# FPGA_7A35T.net
KiCad netlist of a schematic drawn in Altium Designer
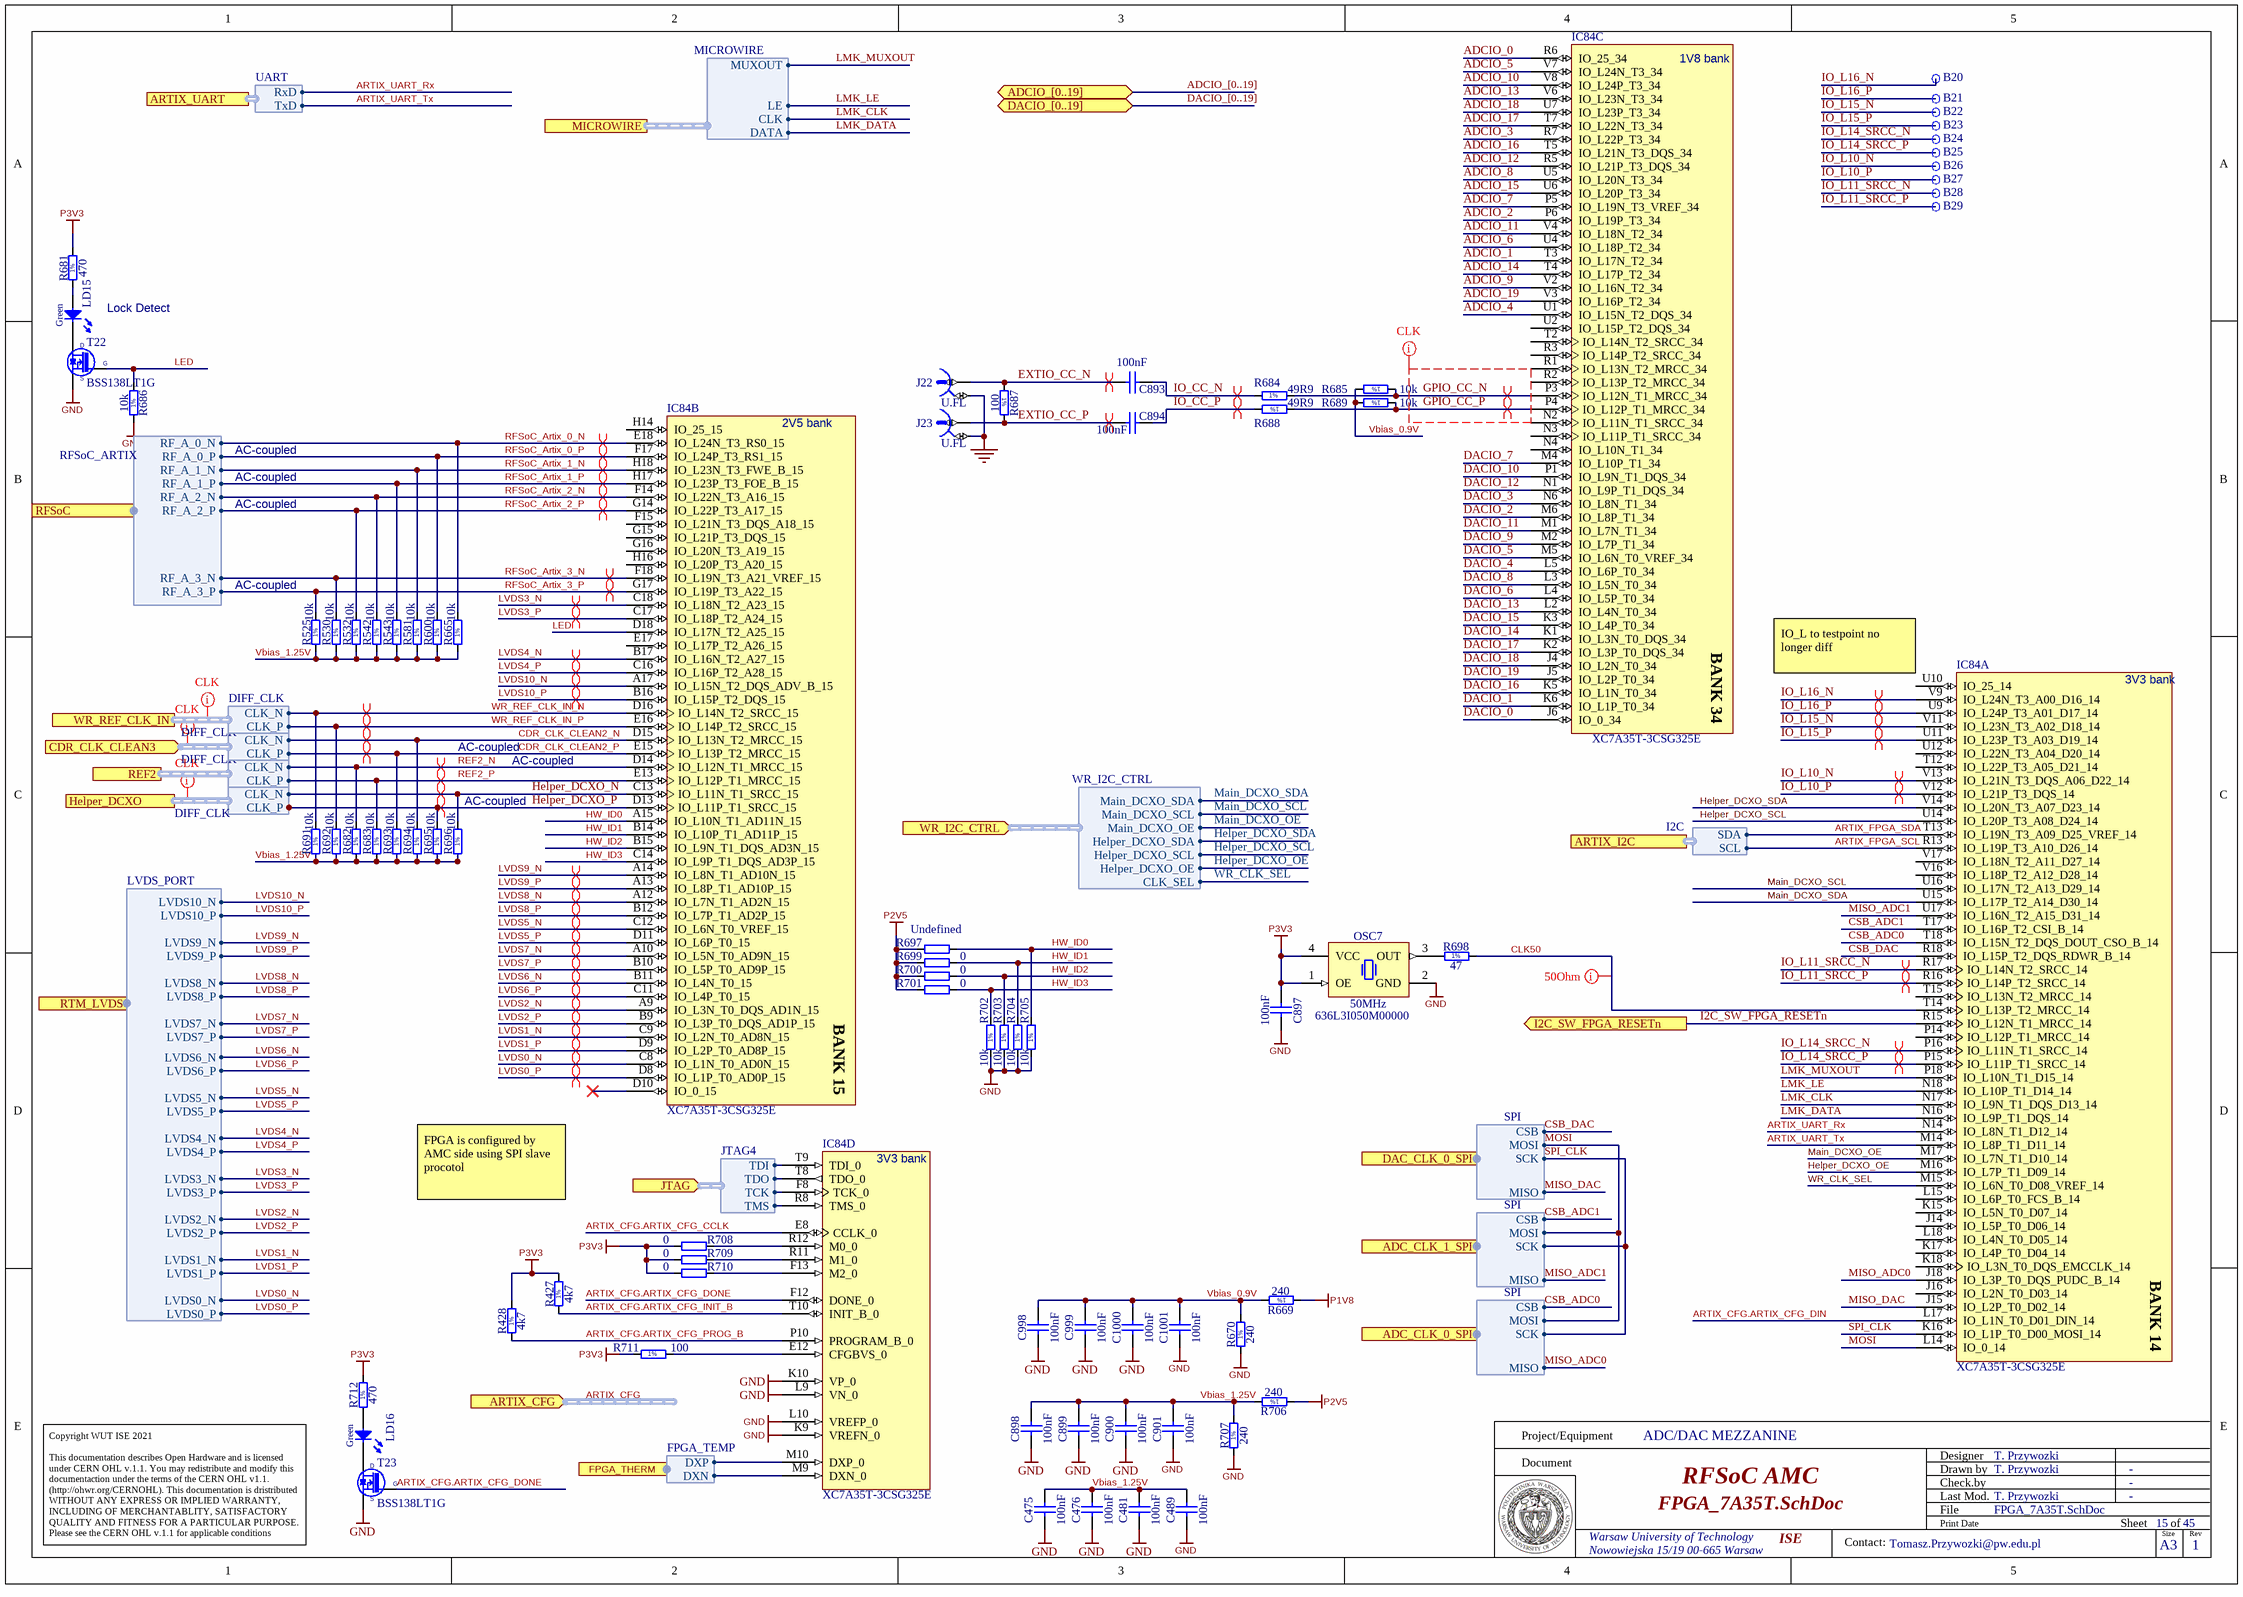
[diagram p0: FPGA_7A35T.SchDoc]

(export (version "E")
  (design (tool "Eeschema 10.0.6"))
  (components
    (comp (ref "B20")
      (value "SMD_PAD_D1MM")
      (footprint "C100")
      (libsource (lib "altium-import") (part "root_0__*"))
    )
    (comp (ref "B21")
      (value "SMD_PAD_D1MM")
      (footprint "C100")
      (libsource (lib "altium-import") (part "root_0__*"))
    )
    (comp (ref "B22")
      (value "SMD_PAD_D1MM")
      (footprint "C100")
      (libsource (lib "altium-import") (part "root_0__*"))
    )
    (comp (ref "B23")
      (value "SMD_PAD_D1MM")
      (footprint "C100")
      (libsource (lib "altium-import") (part "root_0__*"))
    )
    (comp (ref "B24")
      (value "SMD_PAD_D1MM")
      (footprint "C100")
      (libsource (lib "altium-import") (part "root_0__*"))
    )
    (comp (ref "B25")
      (value "SMD_PAD_D1MM")
      (footprint "C100")
      (libsource (lib "altium-import") (part "root_0__*"))
    )
    (comp (ref "B26")
      (value "SMD_PAD_D1MM")
      (footprint "C100")
      (libsource (lib "altium-import") (part "root_0__*"))
    )
    (comp (ref "B27")
      (value "SMD_PAD_D1MM")
      (footprint "C100")
      (libsource (lib "altium-import") (part "root_0__*"))
    )
    (comp (ref "B28")
      (value "SMD_PAD_D1MM")
      (footprint "C100")
      (libsource (lib "altium-import") (part "root_0__*"))
    )
    (comp (ref "B29")
      (value "SMD_PAD_D1MM")
      (footprint "C100")
      (libsource (lib "altium-import") (part "root_0__*"))
    )
    (comp (ref "C475")
      (value "100nF")
      (footprint "CAPC0603X33N")
      (description "Non-polarised capacitor")
      (fields
        (field (name "MANUFACTURER PART NUMBER") "CC0201_100NF_6.3V_10%_X5R")
        (field (name "MANUFACTURER") "GENERIC")
        (field (name "AUTHOR") "CERN DEM JLC")
      )
      (libsource (lib "Capacitors") (part "Capacitor - non polarized"))
    )
    (comp (ref "C476")
      (value "100nF")
      (footprint "CAPC0603X33N")
      (description "Non-polarised capacitor")
      (fields
        (field (name "MANUFACTURER PART NUMBER") "CC0201_100NF_6.3V_10%_X5R")
        (field (name "MANUFACTURER") "GENERIC")
        (field (name "AUTHOR") "CERN DEM JLC")
      )
      (libsource (lib "Capacitors") (part "Capacitor - non polarized"))
    )
    (comp (ref "C481")
      (value "100nF")
      (footprint "CAPC0603X33N")
      (description "Non-polarised capacitor")
      (fields
        (field (name "MANUFACTURER PART NUMBER") "CC0201_100NF_6.3V_10%_X5R")
        (field (name "MANUFACTURER") "GENERIC")
        (field (name "AUTHOR") "CERN DEM JLC")
      )
      (libsource (lib "Capacitors") (part "Capacitor - non polarized"))
    )
    (comp (ref "C489")
      (value "100nF")
      (footprint "CAPC0603X33N")
      (description "Non-polarised capacitor")
      (fields
        (field (name "MANUFACTURER PART NUMBER") "CC0201_100NF_6.3V_10%_X5R")
        (field (name "MANUFACTURER") "GENERIC")
        (field (name "AUTHOR") "CERN DEM JLC")
      )
      (libsource (lib "Capacitors") (part "Capacitor - non polarized"))
    )
    (comp (ref "C893")
      (value "100nF")
      (footprint "CAPC1005X55N")
      (description "Non-polarised capacitor")
      (fields
        (field (name "MANUFACTURER PART NUMBER") "CC0402_100NF_16V_10%_X5R")
        (field (name "MANUFACTURER") "GENERIC")
        (field (name "AUTHOR") "CERN DEM JLC")
      )
      (libsource (lib "Capacitors") (part "Capacitor - non polarized"))
    )
    (comp (ref "C894")
      (value "100nF")
      (footprint "CAPC1005X55N")
      (description "Non-polarised capacitor")
      (fields
        (field (name "MANUFACTURER PART NUMBER") "CC0402_100NF_16V_10%_X5R")
        (field (name "MANUFACTURER") "GENERIC")
        (field (name "AUTHOR") "CERN DEM JLC")
      )
      (libsource (lib "Capacitors") (part "Capacitor - non polarized"))
    )
    (comp (ref "C897")
      (value "100nF")
      (footprint "CAPC0603X33N")
      (description "Non-polarised capacitor")
      (fields
        (field (name "MANUFACTURER PART NUMBER") "CC0201_100NF_6.3V_10%_X5R")
        (field (name "MANUFACTURER") "GENERIC")
        (field (name "AUTHOR") "CERN DEM JLC")
      )
      (libsource (lib "Capacitors") (part "Capacitor - non polarized"))
    )
    (comp (ref "C898")
      (value "100nF")
      (footprint "CAPC0603X33N")
      (description "Non-polarised capacitor")
      (fields
        (field (name "MANUFACTURER PART NUMBER") "CC0201_100NF_6.3V_10%_X5R")
        (field (name "MANUFACTURER") "GENERIC")
        (field (name "AUTHOR") "CERN DEM JLC")
      )
      (libsource (lib "Capacitors") (part "Capacitor - non polarized"))
    )
    (comp (ref "C899")
      (value "100nF")
      (footprint "CAPC0603X33N")
      (description "Non-polarised capacitor")
      (fields
        (field (name "MANUFACTURER PART NUMBER") "CC0201_100NF_6.3V_10%_X5R")
        (field (name "MANUFACTURER") "GENERIC")
        (field (name "AUTHOR") "CERN DEM JLC")
      )
      (libsource (lib "Capacitors") (part "Capacitor - non polarized"))
    )
    (comp (ref "C900")
      (value "100nF")
      (footprint "CAPC0603X33N")
      (description "Non-polarised capacitor")
      (fields
        (field (name "MANUFACTURER PART NUMBER") "CC0201_100NF_6.3V_10%_X5R")
        (field (name "MANUFACTURER") "GENERIC")
        (field (name "AUTHOR") "CERN DEM JLC")
      )
      (libsource (lib "Capacitors") (part "Capacitor - non polarized"))
    )
    (comp (ref "C901")
      (value "100nF")
      (footprint "CAPC0603X33N")
      (description "Non-polarised capacitor")
      (fields
        (field (name "MANUFACTURER PART NUMBER") "CC0201_100NF_6.3V_10%_X5R")
        (field (name "MANUFACTURER") "GENERIC")
        (field (name "AUTHOR") "CERN DEM JLC")
      )
      (libsource (lib "Capacitors") (part "Capacitor - non polarized"))
    )
    (comp (ref "C998")
      (value "100nF")
      (footprint "CAPC0603X33N")
      (description "Non-polarised capacitor")
      (fields
        (field (name "MANUFACTURER PART NUMBER") "CC0201_100NF_6.3V_10%_X5R")
        (field (name "MANUFACTURER") "GENERIC")
        (field (name "AUTHOR") "CERN DEM JLC")
      )
      (libsource (lib "Capacitors") (part "Capacitor - non polarized"))
    )
    (comp (ref "C999")
      (value "100nF")
      (footprint "CAPC0603X33N")
      (description "Non-polarised capacitor")
      (fields
        (field (name "MANUFACTURER PART NUMBER") "CC0201_100NF_6.3V_10%_X5R")
        (field (name "MANUFACTURER") "GENERIC")
        (field (name "AUTHOR") "CERN DEM JLC")
      )
      (libsource (lib "Capacitors") (part "Capacitor - non polarized"))
    )
    (comp (ref "C1000")
      (value "100nF")
      (footprint "CAPC0603X33N")
      (description "Non-polarised capacitor")
      (fields
        (field (name "MANUFACTURER PART NUMBER") "CC0201_100NF_6.3V_10%_X5R")
        (field (name "MANUFACTURER") "GENERIC")
        (field (name "AUTHOR") "CERN DEM JLC")
      )
      (libsource (lib "Capacitors") (part "Capacitor - non polarized"))
    )
    (comp (ref "C1001")
      (value "100nF")
      (footprint "CAPC0603X33N")
      (description "Non-polarised capacitor")
      (fields
        (field (name "MANUFACTURER PART NUMBER") "CC0201_100NF_6.3V_10%_X5R")
        (field (name "MANUFACTURER") "GENERIC")
        (field (name "AUTHOR") "CERN DEM JLC")
      )
      (libsource (lib "Capacitors") (part "Capacitor - non polarized"))
    )
    (comp (ref "IC84")
      (value "XC7A35T-3CSG325E")
      (footprint "CSG325")
      (description "Artix-7 FPGA, 150 User I/Os, 4 GTP, 324-Ball BGA, Speed Grade 3, Extended Grade, Pb-Free")
      (fields (field (name "MANUFACTURER") "Xilinx"))
      (libsource (lib "Altium Content Vault") (part "XLNX-XC7A35T-CSG325"))
    )
    (comp (ref "J22")
      (value "U.FL")
      (footprint "HIROSE_U.FL-R-SMT-1(10)")
      (fields
        (field (name "PART NUMBER") "HIROSE_U.FL-R-SMT-1(10)")
        (field (name "MANUFACTURER") "HIROSE (HRS)")
        (field (name "MANUFACTURER PART NUMBER") "U.FL-R-SMT-1(10)")
        (field (name "AUTHOR") "CERN DEM JLC")
      )
      (libsource (lib "Connectors") (part "Coax_1Male_1Shield"))
    )
    (comp (ref "J23")
      (value "U.FL")
      (footprint "HIROSE_U.FL-R-SMT-1(10)")
      (fields
        (field (name "PART NUMBER") "HIROSE_U.FL-R-SMT-1(10)")
        (field (name "MANUFACTURER") "HIROSE (HRS)")
        (field (name "MANUFACTURER PART NUMBER") "U.FL-R-SMT-1(10)")
        (field (name "AUTHOR") "CERN DEM JLC")
      )
      (libsource (lib "Connectors") (part "Coax_1Male_1Shield"))
    )
    (comp (ref "LD15")
      (value "Green")
      (footprint "LED_KINGBRIGHT_KPH-1608CGCK")
      (description "LED Green 1C 2A")
      (fields
        (field (name "MANUFACTURER PART NUMBER") "KPH-1608CGCK")
        (field (name "MANUFACTURER") "KINGBRIGHT")
        (field (name "AUTHOR") "CERN DEM JLC")
      )
      (libsource (lib "ICs And Semiconductors") (part "LED Green 1C 2A"))
    )
    (comp (ref "LD16")
      (value "Green")
      (footprint "LED_KINGBRIGHT_KPH-1608CGCK")
      (description "LED Green 1C 2A")
      (fields
        (field (name "MANUFACTURER PART NUMBER") "KPH-1608CGCK")
        (field (name "MANUFACTURER") "KINGBRIGHT")
        (field (name "AUTHOR") "CERN DEM JLC")
      )
      (libsource (lib "ICs And Semiconductors") (part "LED Green 1C 2A"))
    )
    (comp (ref "OSC7")
      (value "50MHz")
      (footprint "OSCSC254P320X500X130-4N")
      (description "Oscillator 4 pins 1=OE 2=GND 3=OUT 4=VCC")
      (fields
        (field (name "MANUFACTURER PART NUMBER") "636L3I050M00000")
        (field (name "MANUFACTURER") "CTS ELECTRONIC COMPONENTS")
        (field (name "PART NUMBER") "OSC_50MHZ_CTS_636L3I050M00000")
        (field (name "AUTHOR") "CERN DEM JMW")
      )
      (libsource (lib "ICs And Semiconductors") (part "Oscillator 1OE 2GND 3OUT 4VCC"))
    )
    (comp (ref "R427")
      (value "4k7")
      (footprint "RESC1005X40N")
      (description "Resistor - 1%")
      (fields
        (field (name "MANUFACTURER PART NUMBER") "R0402_4K7_1%_0.0625W_100PPM")
        (field (name "MANUFACTURER") "GENERIC")
        (field (name "AUTHOR") "CERN DEM JLC")
      )
      (libsource (lib "Resistors") (part "Resistor - 1%"))
    )
    (comp (ref "R428")
      (value "4k7")
      (footprint "RESC1005X40N")
      (description "Resistor - 1%")
      (fields
        (field (name "MANUFACTURER PART NUMBER") "R0402_4K7_1%_0.0625W_100PPM")
        (field (name "MANUFACTURER") "GENERIC")
        (field (name "AUTHOR") "CERN DEM JLC")
      )
      (libsource (lib "Resistors") (part "Resistor - 1%"))
    )
    (comp (ref "R525")
      (value "10k")
      (footprint "RESC1005X40N")
      (description "Resistor - 1%")
      (fields
        (field (name "MANUFACTURER PART NUMBER") "R0402_10K_1%_0.0625W_100PPM")
        (field (name "MANUFACTURER") "GENERIC")
        (field (name "AUTHOR") "CERN DEM JLC")
      )
      (libsource (lib "Resistors") (part "Resistor - 1%"))
    )
    (comp (ref "R530")
      (value "10k")
      (footprint "RESC1005X40N")
      (description "Resistor - 1%")
      (fields
        (field (name "MANUFACTURER PART NUMBER") "R0402_10K_1%_0.0625W_100PPM")
        (field (name "MANUFACTURER") "GENERIC")
        (field (name "AUTHOR") "CERN DEM JLC")
      )
      (libsource (lib "Resistors") (part "Resistor - 1%"))
    )
    (comp (ref "R532")
      (value "10k")
      (footprint "RESC1005X40N")
      (description "Resistor - 1%")
      (fields
        (field (name "MANUFACTURER PART NUMBER") "R0402_10K_1%_0.0625W_100PPM")
        (field (name "MANUFACTURER") "GENERIC")
        (field (name "AUTHOR") "CERN DEM JLC")
      )
      (libsource (lib "Resistors") (part "Resistor - 1%"))
    )
    (comp (ref "R542")
      (value "10k")
      (footprint "RESC1005X40N")
      (description "Resistor - 1%")
      (fields
        (field (name "MANUFACTURER PART NUMBER") "R0402_10K_1%_0.0625W_100PPM")
        (field (name "MANUFACTURER") "GENERIC")
        (field (name "AUTHOR") "CERN DEM JLC")
      )
      (libsource (lib "Resistors") (part "Resistor - 1%"))
    )
    (comp (ref "R543")
      (value "10k")
      (footprint "RESC1005X40N")
      (description "Resistor - 1%")
      (fields
        (field (name "MANUFACTURER PART NUMBER") "R0402_10K_1%_0.0625W_100PPM")
        (field (name "MANUFACTURER") "GENERIC")
        (field (name "AUTHOR") "CERN DEM JLC")
      )
      (libsource (lib "Resistors") (part "Resistor - 1%"))
    )
    (comp (ref "R581")
      (value "10k")
      (footprint "RESC1005X40N")
      (description "Resistor - 1%")
      (fields
        (field (name "MANUFACTURER PART NUMBER") "R0402_10K_1%_0.0625W_100PPM")
        (field (name "MANUFACTURER") "GENERIC")
        (field (name "AUTHOR") "CERN DEM JLC")
      )
      (libsource (lib "Resistors") (part "Resistor - 1%"))
    )
    (comp (ref "R600")
      (value "10k")
      (footprint "RESC1005X40N")
      (description "Resistor - 1%")
      (fields
        (field (name "MANUFACTURER PART NUMBER") "R0402_10K_1%_0.0625W_100PPM")
        (field (name "MANUFACTURER") "GENERIC")
        (field (name "AUTHOR") "CERN DEM JLC")
      )
      (libsource (lib "Resistors") (part "Resistor - 1%"))
    )
    (comp (ref "R665")
      (value "10k")
      (footprint "RESC1005X40N")
      (description "Resistor - 1%")
      (fields
        (field (name "MANUFACTURER PART NUMBER") "R0402_10K_1%_0.0625W_100PPM")
        (field (name "MANUFACTURER") "GENERIC")
        (field (name "AUTHOR") "CERN DEM JLC")
      )
      (libsource (lib "Resistors") (part "Resistor - 1%"))
    )
    (comp (ref "R669")
      (value "240")
      (footprint "RESC1005X40N")
      (description "Resistor - 1%")
      (fields
        (field (name "MANUFACTURER PART NUMBER") "R0402_240R_1%_0.0625W_100PPM")
        (field (name "MANUFACTURER") "GENERIC")
        (field (name "AUTHOR") "CERN DEM JLC")
      )
      (libsource (lib "Resistors") (part "Resistor - 1%"))
    )
    (comp (ref "R670")
      (value "240")
      (footprint "RESC1005X40N")
      (description "Resistor - 1%")
      (fields
        (field (name "MANUFACTURER PART NUMBER") "R0402_240R_1%_0.0625W_100PPM")
        (field (name "MANUFACTURER") "GENERIC")
        (field (name "AUTHOR") "CERN DEM JLC")
      )
      (libsource (lib "Resistors") (part "Resistor - 1%"))
    )
    (comp (ref "R681")
      (value "470")
      (footprint "RESC1005X40N")
      (description "Resistor - 1%")
      (fields
        (field (name "MANUFACTURER PART NUMBER") "R0402_470R_1%_0.0625W_100PPM")
        (field (name "MANUFACTURER") "GENERIC")
        (field (name "AUTHOR") "CERN DEM JLC")
      )
      (libsource (lib "Resistors") (part "Resistor - 1%"))
    )
    (comp (ref "R682")
      (value "10k")
      (footprint "RESC1005X40N")
      (description "Resistor - 1%")
      (fields
        (field (name "MANUFACTURER PART NUMBER") "R0402_10K_1%_0.0625W_100PPM")
        (field (name "MANUFACTURER") "GENERIC")
        (field (name "AUTHOR") "CERN DEM JLC")
      )
      (libsource (lib "Resistors") (part "Resistor - 1%"))
    )
    (comp (ref "R683")
      (value "10k")
      (footprint "RESC1005X40N")
      (description "Resistor - 1%")
      (fields
        (field (name "MANUFACTURER PART NUMBER") "R0402_10K_1%_0.0625W_100PPM")
        (field (name "MANUFACTURER") "GENERIC")
        (field (name "AUTHOR") "CERN DEM JLC")
      )
      (libsource (lib "Resistors") (part "Resistor - 1%"))
    )
    (comp (ref "R684")
      (value "49R9")
      (footprint "RESC1005X40N")
      (description "Resistor - 1%")
      (fields
        (field (name "MANUFACTURER PART NUMBER") "R0402_49R9_1%_0.0625W_100PPM")
        (field (name "MANUFACTURER") "GENERIC")
        (field (name "AUTHOR") "CERN DEM JLC")
      )
      (libsource (lib "Resistors") (part "Resistor - 1%"))
    )
    (comp (ref "R685")
      (value "10k")
      (footprint "RESC1005X40N")
      (description "Resistor - 1%")
      (fields
        (field (name "MANUFACTURER PART NUMBER") "R0402_10K_1%_0.0625W_100PPM")
        (field (name "MANUFACTURER") "GENERIC")
        (field (name "AUTHOR") "CERN DEM JLC")
      )
      (libsource (lib "Resistors") (part "Resistor - 1%"))
    )
    (comp (ref "R686")
      (value "10k")
      (footprint "RESC1005X40N")
      (description "Resistor - 1%")
      (fields
        (field (name "MANUFACTURER PART NUMBER") "R0402_10K_1%_0.0625W_100PPM")
        (field (name "MANUFACTURER") "GENERIC")
        (field (name "AUTHOR") "CERN DEM JLC")
      )
      (libsource (lib "Resistors") (part "Resistor - 1%"))
    )
    (comp (ref "R687")
      (value "100")
      (footprint "RESC1005X40N")
      (description "Resistor - 1%")
      (fields
        (field (name "MANUFACTURER PART NUMBER") "R0402_100R_1%_0.0625W_100PPM")
        (field (name "MANUFACTURER") "GENERIC")
        (field (name "AUTHOR") "CERN DEM JLC")
      )
      (libsource (lib "Resistors") (part "Resistor - 1%"))
    )
    (comp (ref "R688")
      (value "49R9")
      (footprint "RESC1005X40N")
      (description "Resistor - 1%")
      (fields
        (field (name "MANUFACTURER PART NUMBER") "R0402_49R9_1%_0.0625W_100PPM")
        (field (name "MANUFACTURER") "GENERIC")
        (field (name "AUTHOR") "CERN DEM JLC")
      )
      (libsource (lib "Resistors") (part "Resistor - 1%"))
    )
    (comp (ref "R689")
      (value "10k")
      (footprint "RESC1005X40N")
      (description "Resistor - 1%")
      (fields
        (field (name "MANUFACTURER PART NUMBER") "R0402_10K_1%_0.0625W_100PPM")
        (field (name "MANUFACTURER") "GENERIC")
        (field (name "AUTHOR") "CERN DEM JLC")
      )
      (libsource (lib "Resistors") (part "Resistor - 1%"))
    )
    (comp (ref "R691")
      (value "10k")
      (footprint "RESC1005X40N")
      (description "Resistor - 1%")
      (fields
        (field (name "MANUFACTURER PART NUMBER") "R0402_10K_1%_0.0625W_100PPM")
        (field (name "MANUFACTURER") "GENERIC")
        (field (name "AUTHOR") "CERN DEM JLC")
      )
      (libsource (lib "Resistors") (part "Resistor - 1%"))
    )
    (comp (ref "R692")
      (value "10k")
      (footprint "RESC1005X40N")
      (description "Resistor - 1%")
      (fields
        (field (name "MANUFACTURER PART NUMBER") "R0402_10K_1%_0.0625W_100PPM")
        (field (name "MANUFACTURER") "GENERIC")
        (field (name "AUTHOR") "CERN DEM JLC")
      )
      (libsource (lib "Resistors") (part "Resistor - 1%"))
    )
    (comp (ref "R693")
      (value "10k")
      (footprint "RESC1005X40N")
      (description "Resistor - 1%")
      (fields
        (field (name "MANUFACTURER PART NUMBER") "R0402_10K_1%_0.0625W_100PPM")
        (field (name "MANUFACTURER") "GENERIC")
        (field (name "AUTHOR") "CERN DEM JLC")
      )
      (libsource (lib "Resistors") (part "Resistor - 1%"))
    )
    (comp (ref "R694")
      (value "10k")
      (footprint "RESC1005X40N")
      (description "Resistor - 1%")
      (fields
        (field (name "MANUFACTURER PART NUMBER") "R0402_10K_1%_0.0625W_100PPM")
        (field (name "MANUFACTURER") "GENERIC")
        (field (name "AUTHOR") "CERN DEM JLC")
      )
      (libsource (lib "Resistors") (part "Resistor - 1%"))
    )
    (comp (ref "R695")
      (value "10k")
      (footprint "RESC1005X40N")
      (description "Resistor - 1%")
      (fields
        (field (name "MANUFACTURER PART NUMBER") "R0402_10K_1%_0.0625W_100PPM")
        (field (name "MANUFACTURER") "GENERIC")
        (field (name "AUTHOR") "CERN DEM JLC")
      )
      (libsource (lib "Resistors") (part "Resistor - 1%"))
    )
    (comp (ref "R696")
      (value "10k")
      (footprint "RESC1005X40N")
      (description "Resistor - 1%")
      (fields
        (field (name "MANUFACTURER PART NUMBER") "R0402_10K_1%_0.0625W_100PPM")
        (field (name "MANUFACTURER") "GENERIC")
        (field (name "AUTHOR") "CERN DEM JLC")
      )
      (libsource (lib "Resistors") (part "Resistor - 1%"))
    )
    (comp (ref "R697")
      (value "Undefined")
      (footprint "RESC1005X40N")
      (description "Resistor")
      (fields
        (field (name "MANUFACTURER PART NUMBER") "R0402_NO-VALUE")
        (field (name "AUTHOR") "CERN DEM JLC")
      )
      (libsource (lib "Resistors") (part "Resistor"))
    )
    (comp (ref "R698")
      (value "47")
      (footprint "RESC1005X40N")
      (description "Resistor - 1%")
      (fields
        (field (name "PART NUMBER") "R0402_47R_1%_0.0625W_100PPM")
        (field (name "POWER") "0.0625W")
        (field (name "AUTHOR") "CERN DEM JLC")
      )
      (libsource (lib "Resistors") (part "Resistor - 1%"))
    )
    (comp (ref "R699")
      (value "0")
      (footprint "RESC1005X40N")
      (description "Resistor")
      (fields
        (field (name "MANUFACTURER PART NUMBER") "R0402_0R_JUMPER")
        (field (name "MANUFACTURER") "GENERIC")
        (field (name "AUTHOR") "CERN DEM JLC")
      )
      (libsource (lib "Resistors") (part "Resistor"))
    )
    (comp (ref "R700")
      (value "0")
      (footprint "RESC1005X40N")
      (description "Resistor")
      (fields
        (field (name "MANUFACTURER PART NUMBER") "R0402_0R_JUMPER")
        (field (name "MANUFACTURER") "GENERIC")
        (field (name "AUTHOR") "CERN DEM JLC")
      )
      (libsource (lib "Resistors") (part "Resistor"))
    )
    (comp (ref "R701")
      (value "0")
      (footprint "RESC1005X40N")
      (description "Resistor")
      (fields
        (field (name "MANUFACTURER PART NUMBER") "R0402_0R_JUMPER")
        (field (name "MANUFACTURER") "GENERIC")
        (field (name "AUTHOR") "CERN DEM JLC")
      )
      (libsource (lib "Resistors") (part "Resistor"))
    )
    (comp (ref "R702")
      (value "10k")
      (footprint "RESC1005X40N")
      (description "Resistor - 1%")
      (fields
        (field (name "MANUFACTURER PART NUMBER") "R0402_10K_1%_0.0625W_100PPM")
        (field (name "MANUFACTURER") "GENERIC")
        (field (name "AUTHOR") "CERN DEM JLC")
      )
      (libsource (lib "Resistors") (part "Resistor - 1%"))
    )
    (comp (ref "R703")
      (value "10k")
      (footprint "RESC1005X40N")
      (description "Resistor - 1%")
      (fields
        (field (name "MANUFACTURER PART NUMBER") "R0402_10K_1%_0.0625W_100PPM")
        (field (name "MANUFACTURER") "GENERIC")
        (field (name "AUTHOR") "CERN DEM JLC")
      )
      (libsource (lib "Resistors") (part "Resistor - 1%"))
    )
    (comp (ref "R704")
      (value "10k")
      (footprint "RESC1005X40N")
      (description "Resistor - 1%")
      (fields
        (field (name "MANUFACTURER PART NUMBER") "R0402_10K_1%_0.0625W_100PPM")
        (field (name "MANUFACTURER") "GENERIC")
        (field (name "AUTHOR") "CERN DEM JLC")
      )
      (libsource (lib "Resistors") (part "Resistor - 1%"))
    )
    (comp (ref "R705")
      (value "10k")
      (footprint "RESC1005X40N")
      (description "Resistor - 1%")
      (fields
        (field (name "MANUFACTURER PART NUMBER") "R0402_10K_1%_0.0625W_100PPM")
        (field (name "MANUFACTURER") "GENERIC")
        (field (name "AUTHOR") "CERN DEM JLC")
      )
      (libsource (lib "Resistors") (part "Resistor - 1%"))
    )
    (comp (ref "R706")
      (value "240")
      (footprint "RESC1005X40N")
      (description "Resistor - 1%")
      (fields
        (field (name "MANUFACTURER PART NUMBER") "R0402_240R_1%_0.0625W_100PPM")
        (field (name "MANUFACTURER") "GENERIC")
        (field (name "AUTHOR") "CERN DEM JLC")
      )
      (libsource (lib "Resistors") (part "Resistor - 1%"))
    )
    (comp (ref "R707")
      (value "240")
      (footprint "RESC1005X40N")
      (description "Resistor - 1%")
      (fields
        (field (name "MANUFACTURER PART NUMBER") "R0402_240R_1%_0.0625W_100PPM")
        (field (name "MANUFACTURER") "GENERIC")
        (field (name "AUTHOR") "CERN DEM JLC")
      )
      (libsource (lib "Resistors") (part "Resistor - 1%"))
    )
    (comp (ref "R708")
      (value "0")
      (footprint "RESC1005X40N")
      (description "Resistor")
      (fields
        (field (name "MANUFACTURER PART NUMBER") "R0402_0R_JUMPER")
        (field (name "MANUFACTURER") "GENERIC")
        (field (name "AUTHOR") "CERN DEM JLC")
      )
      (libsource (lib "Resistors") (part "Resistor"))
    )
    (comp (ref "R709")
      (value "0")
      (footprint "RESC1005X40N")
      (description "Resistor")
      (fields
        (field (name "MANUFACTURER PART NUMBER") "R0402_0R_JUMPER")
        (field (name "MANUFACTURER") "GENERIC")
        (field (name "AUTHOR") "CERN DEM JLC")
      )
      (libsource (lib "Resistors") (part "Resistor"))
    )
    (comp (ref "R710")
      (value "0")
      (footprint "RESC1005X40N")
      (description "Resistor")
      (fields
        (field (name "MANUFACTURER PART NUMBER") "R0402_0R_JUMPER")
        (field (name "MANUFACTURER") "GENERIC")
        (field (name "AUTHOR") "CERN DEM JLC")
      )
      (libsource (lib "Resistors") (part "Resistor"))
    )
    (comp (ref "R711")
      (value "100")
      (footprint "RESC1005X40N")
      (description "Resistor - 1%")
      (fields
        (field (name "MANUFACTURER PART NUMBER") "R0402_100R_1%_0.1W_100PPM_50V")
        (field (name "MANUFACTURER") "GENERIC")
        (field (name "AUTHOR") "CERN DEM JLC")
      )
      (libsource (lib "Resistors") (part "Resistor - 1%"))
    )
    (comp (ref "R712")
      (value "470")
      (footprint "RESC1005X40N")
      (description "Resistor - 1%")
      (fields
        (field (name "MANUFACTURER PART NUMBER") "R0402_470R_1%_0.0625W_100PPM")
        (field (name "MANUFACTURER") "GENERIC")
        (field (name "AUTHOR") "CERN DEM JLC")
      )
      (libsource (lib "Resistors") (part "Resistor - 1%"))
    )
    (comp (ref "T22")
      (value "BSS138LT1G")
      (footprint "SOT95P240X110-3N")
      (description "N-CHANNEL MOSFET WITH DIODE")
      (fields (field (name "MANUFACTURER") "ON SEMICONDUCTOR") (field (name "AUTHOR") "CERN DEM JLC"))
      (libsource (lib "ICs And Semiconductors") (part "N-MOSFET-D 1G 2S 3D"))
    )
    (comp (ref "T23")
      (value "BSS138LT1G")
      (footprint "SOT95P240X110-3N")
      (description "N-CHANNEL MOSFET WITH DIODE")
      (fields (field (name "MANUFACTURER") "ON SEMICONDUCTOR") (field (name "AUTHOR") "CERN DEM JLC"))
      (libsource (lib "ICs And Semiconductors") (part "N-MOSFET-D 1G 2S 3D"))
    )
  )
  (nets
    (net (code "14") (name "/ADCIO_0") (class "Default")
      (node (ref "IC84") (pin "R6") (pinfunction "IO_25_34_R6") (pintype "bidirectional"))
    )
    (net (code "15") (name "/ADCIO_1") (class "Default")
      (node (ref "IC84") (pin "T3") (pinfunction "IO_L17N_T2_34_T3") (pintype "bidirectional"))
    )
    (net (code "16") (name "/ADCIO_2") (class "Default")
      (node (ref "IC84") (pin "P6") (pinfunction "IO_L19P_T3_34_P6") (pintype "bidirectional"))
    )
    (net (code "17") (name "/ADCIO_3") (class "Default")
      (node (ref "IC84") (pin "R7") (pinfunction "IO_L22P_T3_34_R7") (pintype "bidirectional"))
    )
    (net (code "18") (name "/ADCIO_4") (class "Default")
      (node (ref "IC84") (pin "U1") (pinfunction "IO_L15N_T2_DQS_34_U1") (pintype "bidirectional"))
    )
    (net (code "19") (name "/ADCIO_5") (class "Default")
      (node (ref "IC84") (pin "V7") (pinfunction "IO_L24N_T3_34_V7") (pintype "bidirectional"))
    )
    (net (code "20") (name "/ADCIO_6") (class "Default")
      (node (ref "IC84") (pin "U4") (pinfunction "IO_L18P_T2_34_U4") (pintype "bidirectional"))
    )
    (net (code "21") (name "/ADCIO_7") (class "Default")
      (node (ref "IC84") (pin "P5") (pinfunction "IO_L19N_T3_VREF_34_P5") (pintype "bidirectional"))
    )
    (net (code "22") (name "/ADCIO_8") (class "Default")
      (node (ref "IC84") (pin "U5") (pinfunction "IO_L20N_T3_34_U5") (pintype "bidirectional"))
    )
    (net (code "23") (name "/ADCIO_9") (class "Default")
      (node (ref "IC84") (pin "V2") (pinfunction "IO_L16N_T2_34_V2") (pintype "bidirectional"))
    )
    (net (code "24") (name "/ADCIO_10") (class "Default")
      (node (ref "IC84") (pin "V8") (pinfunction "IO_L24P_T3_34_V8") (pintype "bidirectional"))
    )
    (net (code "25") (name "/ADCIO_11") (class "Default")
      (node (ref "IC84") (pin "V4") (pinfunction "IO_L18N_T2_34_V4") (pintype "bidirectional"))
    )
    (net (code "26") (name "/ADCIO_12") (class "Default")
      (node (ref "IC84") (pin "R5") (pinfunction "IO_L21P_T3_DQS_34_R5") (pintype "bidirectional"))
    )
    (net (code "27") (name "/ADCIO_13") (class "Default")
      (node (ref "IC84") (pin "V6") (pinfunction "IO_L23N_T3_34_V6") (pintype "bidirectional"))
    )
    (net (code "28") (name "/ADCIO_14") (class "Default")
      (node (ref "IC84") (pin "T4") (pinfunction "IO_L17P_T2_34_T4") (pintype "bidirectional"))
    )
    (net (code "29") (name "/ADCIO_15") (class "Default")
      (node (ref "IC84") (pin "U6") (pinfunction "IO_L20P_T3_34_U6") (pintype "bidirectional"))
    )
    (net (code "30") (name "/ADCIO_16") (class "Default")
      (node (ref "IC84") (pin "T5") (pinfunction "IO_L21N_T3_DQS_34_T5") (pintype "bidirectional"))
    )
    (net (code "31") (name "/ADCIO_17") (class "Default")
      (node (ref "IC84") (pin "T7") (pinfunction "IO_L22N_T3_34_T7") (pintype "bidirectional"))
    )
    (net (code "32") (name "/ADCIO_18") (class "Default")
      (node (ref "IC84") (pin "U7") (pinfunction "IO_L23P_T3_34_U7") (pintype "bidirectional"))
    )
    (net (code "33") (name "/ADCIO_19") (class "Default")
      (node (ref "IC84") (pin "V3") (pinfunction "IO_L16P_T2_34_V3") (pintype "bidirectional"))
    )
    (net (code "35") (name "/ARTIX_CFG.ARTIX_CFG_CCLK") (class "Default")
      (node (ref "IC84") (pin "E8") (pinfunction "CCLK_0_E8") (pintype "bidirectional"))
    )
    (net (code "36") (name "/ARTIX_CFG.ARTIX_CFG_DIN") (class "Default")
      (node (ref "IC84") (pin "L17") (pinfunction "IO_L1N_T0_D01_DIN_14_L17") (pintype "bidirectional"))
    )
    (net (code "37") (name "/ARTIX_CFG.ARTIX_CFG_DONE") (class "Default")
      (node (ref "IC84") (pin "F12") (pinfunction "DONE_0_F12") (pintype "bidirectional"))
      (node (ref "T23") (pin "1") (pinfunction "G_1") (pintype "passive"))
    )
    (net (code "38") (name "/ARTIX_CFG.ARTIX_CFG_INIT_B") (class "Default")
      (node (ref "IC84") (pin "T10") (pinfunction "INIT_B_0_T10") (pintype "bidirectional"))
      (node (ref "R427") (pin "1") (pinfunction "1_1") (pintype "passive"))
    )
    (net (code "39") (name "/ARTIX_CFG.ARTIX_CFG_PROG_B") (class "Default")
      (node (ref "IC84") (pin "P10") (pinfunction "PROGRAM_B_0_P10") (pintype "input"))
      (node (ref "R428") (pin "1") (pinfunction "1_1") (pintype "passive"))
    )
    (net (code "40") (name "/ARTIX_FPGA_SCL") (class "Default")
      (node (ref "IC84") (pin "R13") (pinfunction "IO_L19P_T3_A10_D26_14_R13") (pintype "bidirectional"))
    )
    (net (code "41") (name "/ARTIX_FPGA_SDA") (class "Default")
      (node (ref "IC84") (pin "T13") (pinfunction "IO_L19N_T3_A09_D25_VREF_14_T13") (pintype "bidirectional"))
    )
    (net (code "42") (name "/ARTIX_UART_Rx") (class "Default")
      (node (ref "IC84") (pin "N14") (pinfunction "IO_L8N_T1_D12_14_N14") (pintype "bidirectional"))
    )
    (net (code "43") (name "/ARTIX_UART_Tx") (class "Default")
      (node (ref "IC84") (pin "M14") (pinfunction "IO_L8P_T1_D11_14_M14") (pintype "bidirectional"))
    )
    (net (code "44") (name "/CDR_CLK_CLEAN2_N") (class "Default")
      (node (ref "IC84") (pin "D15") (pinfunction "IO_L13N_T2_MRCC_15_D15") (pintype "bidirectional"))
      (node (ref "R694") (pin "2") (pinfunction "2_2") (pintype "passive"))
    )
    (net (code "45") (name "/CDR_CLK_CLEAN2_P") (class "Default")
      (node (ref "IC84") (pin "E15") (pinfunction "IO_L13P_T2_MRCC_15_E15") (pintype "bidirectional"))
      (node (ref "R693") (pin "2") (pinfunction "2_2") (pintype "passive"))
    )
    (net (code "47") (name "/CLK50") (class "Default")
      (node (ref "IC84") (pin "T14") (pinfunction "IO_L13P_T2_MRCC_14_T14") (pintype "bidirectional"))
      (node (ref "R698") (pin "2") (pinfunction "2_2") (pintype "passive"))
    )
    (net (code "48") (name "/CSB_ADC0") (class "Default")
      (node (ref "IC84") (pin "T18") (pinfunction "IO_L15N_T2_DQS_DOUT_CSO_B_14_T18") (pintype "bidirectional"))
    )
    (net (code "49") (name "/CSB_ADC1") (class "Default")
      (node (ref "IC84") (pin "T17") (pinfunction "IO_L16P_T2_CSI_B_14_T17") (pintype "bidirectional"))
    )
    (net (code "50") (name "/CSB_DAC") (class "Default")
      (node (ref "IC84") (pin "R18") (pinfunction "IO_L15P_T2_DQS_RDWR_B_14_R18") (pintype "bidirectional"))
    )
    (net (code "51") (name "/DACIO_0") (class "Default")
      (node (ref "IC84") (pin "J6") (pinfunction "IO_0_34_J6") (pintype "bidirectional"))
    )
    (net (code "52") (name "/DACIO_1") (class "Default")
      (node (ref "IC84") (pin "K6") (pinfunction "IO_L1P_T0_34_K6") (pintype "bidirectional"))
    )
    (net (code "53") (name "/DACIO_2") (class "Default")
      (node (ref "IC84") (pin "M6") (pinfunction "IO_L8P_T1_34_M6") (pintype "bidirectional"))
    )
    (net (code "54") (name "/DACIO_3") (class "Default")
      (node (ref "IC84") (pin "N6") (pinfunction "IO_L8N_T1_34_N6") (pintype "bidirectional"))
    )
    (net (code "55") (name "/DACIO_4") (class "Default")
      (node (ref "IC84") (pin "L5") (pinfunction "IO_L6P_T0_34_L5") (pintype "bidirectional"))
    )
    (net (code "56") (name "/DACIO_5") (class "Default")
      (node (ref "IC84") (pin "M5") (pinfunction "IO_L6N_T0_VREF_34_M5") (pintype "bidirectional"))
    )
    (net (code "57") (name "/DACIO_6") (class "Default")
      (node (ref "IC84") (pin "L4") (pinfunction "IO_L5P_T0_34_L4") (pintype "bidirectional"))
    )
    (net (code "58") (name "/DACIO_7") (class "Default")
      (node (ref "IC84") (pin "M4") (pinfunction "IO_L10P_T1_34_M4") (pintype "bidirectional"))
    )
    (net (code "59") (name "/DACIO_8") (class "Default")
      (node (ref "IC84") (pin "L3") (pinfunction "IO_L5N_T0_34_L3") (pintype "bidirectional"))
    )
    (net (code "60") (name "/DACIO_9") (class "Default")
      (node (ref "IC84") (pin "M2") (pinfunction "IO_L7P_T1_34_M2") (pintype "bidirectional"))
    )
    (net (code "61") (name "/DACIO_10") (class "Default")
      (node (ref "IC84") (pin "P1") (pinfunction "IO_L9N_T1_DQS_34_P1") (pintype "bidirectional"))
    )
    (net (code "62") (name "/DACIO_11") (class "Default")
      (node (ref "IC84") (pin "M1") (pinfunction "IO_L7N_T1_34_M1") (pintype "bidirectional"))
    )
    (net (code "63") (name "/DACIO_12") (class "Default")
      (node (ref "IC84") (pin "N1") (pinfunction "IO_L9P_T1_DQS_34_N1") (pintype "bidirectional"))
    )
    (net (code "64") (name "/DACIO_13") (class "Default")
      (node (ref "IC84") (pin "L2") (pinfunction "IO_L4N_T0_34_L2") (pintype "bidirectional"))
    )
    (net (code "65") (name "/DACIO_14") (class "Default")
      (node (ref "IC84") (pin "K1") (pinfunction "IO_L3N_T0_DQS_34_K1") (pintype "bidirectional"))
    )
    (net (code "66") (name "/DACIO_15") (class "Default")
      (node (ref "IC84") (pin "K3") (pinfunction "IO_L4P_T0_34_K3") (pintype "bidirectional"))
    )
    (net (code "67") (name "/DACIO_16") (class "Default")
      (node (ref "IC84") (pin "K5") (pinfunction "IO_L1N_T0_34_K5") (pintype "bidirectional"))
    )
    (net (code "68") (name "/DACIO_17") (class "Default")
      (node (ref "IC84") (pin "K2") (pinfunction "IO_L3P_T0_DQS_34_K2") (pintype "bidirectional"))
    )
    (net (code "69") (name "/DACIO_18") (class "Default")
      (node (ref "IC84") (pin "J4") (pinfunction "IO_L2N_T0_34_J4") (pintype "bidirectional"))
    )
    (net (code "70") (name "/DACIO_19") (class "Default")
      (node (ref "IC84") (pin "J5") (pinfunction "IO_L2P_T0_34_J5") (pintype "bidirectional"))
    )
    (net (code "72") (name "/DXN") (class "Default")
      (node (ref "IC84") (pin "M9") (pinfunction "DXN_0_M9") (pintype "input"))
    )
    (net (code "73") (name "/DXP") (class "Default")
      (node (ref "IC84") (pin "M10") (pinfunction "DXP_0_M10") (pintype "input"))
    )
    (net (code "74") (name "/EXTIO_CC_N") (class "Default")
      (node (ref "C893") (pin "1") (pinfunction "1_1") (pintype "passive"))
      (node (ref "J22") (pin "1") (pinfunction "1_1") (pintype "bidirectional"))
      (node (ref "R687") (pin "1") (pinfunction "1_1") (pintype "passive"))
    )
    (net (code "75") (name "/EXTIO_CC_P") (class "Default")
      (node (ref "C894") (pin "1") (pinfunction "1_1") (pintype "passive"))
      (node (ref "J23") (pin "1") (pinfunction "1_1") (pintype "bidirectional"))
      (node (ref "R687") (pin "2") (pinfunction "2_2") (pintype "passive"))
    )
    (net (code "76") (name "/GPIO_CC_N") (class "Default")
      (node (ref "IC84") (pin "P3") (pinfunction "IO_L12N_T1_MRCC_34_P3") (pintype "bidirectional"))
      (node (ref "R684") (pin "2") (pinfunction "2_2") (pintype "passive"))
      (node (ref "R685") (pin "1") (pinfunction "1_1") (pintype "passive"))
    )
    (net (code "77") (name "/GPIO_CC_P") (class "Default")
      (node (ref "IC84") (pin "P4") (pinfunction "IO_L12P_T1_MRCC_34_P4") (pintype "bidirectional"))
      (node (ref "R688") (pin "1") (pinfunction "1_1") (pintype "passive"))
      (node (ref "R689") (pin "1") (pinfunction "1_1") (pintype "passive"))
    )
    (net (code "78") (name "/HW_ID0") (class "Default")
      (node (ref "IC84") (pin "A15") (pinfunction "IO_L10N_T1_AD11N_15_A15") (pintype "bidirectional"))
      (node (ref "R697") (pin "2") (pinfunction "2_2") (pintype "passive"))
      (node (ref "R705") (pin "2") (pinfunction "2_2") (pintype "passive"))
    )
    (net (code "79") (name "/HW_ID1") (class "Default")
      (node (ref "IC84") (pin "B14") (pinfunction "IO_L10P_T1_AD11P_15_B14") (pintype "bidirectional"))
      (node (ref "R699") (pin "2") (pinfunction "2_2") (pintype "passive"))
      (node (ref "R704") (pin "2") (pinfunction "2_2") (pintype "passive"))
    )
    (net (code "80") (name "/HW_ID2") (class "Default")
      (node (ref "IC84") (pin "B15") (pinfunction "IO_L9N_T1_DQS_AD3N_15_B15") (pintype "bidirectional"))
      (node (ref "R700") (pin "2") (pinfunction "2_2") (pintype "passive"))
      (node (ref "R703") (pin "2") (pinfunction "2_2") (pintype "passive"))
    )
    (net (code "81") (name "/HW_ID3") (class "Default")
      (node (ref "IC84") (pin "C14") (pinfunction "IO_L9P_T1_DQS_AD3P_15_C14") (pintype "bidirectional"))
      (node (ref "R701") (pin "2") (pinfunction "2_2") (pintype "passive"))
      (node (ref "R702") (pin "2") (pinfunction "2_2") (pintype "passive"))
    )
    (net (code "82") (name "/Helper_DCXO_N") (class "Default")
      (node (ref "IC84") (pin "C13") (pinfunction "IO_L11N_T1_SRCC_15_C13") (pintype "bidirectional"))
      (node (ref "R696") (pin "2") (pinfunction "2_2") (pintype "passive"))
    )
    (net (code "83") (name "/Helper_DCXO_OE") (class "Default")
      (node (ref "IC84") (pin "M16") (pinfunction "IO_L7P_T1_D09_14_M16") (pintype "bidirectional"))
    )
    (net (code "84") (name "/Helper_DCXO_P") (class "Default")
      (node (ref "IC84") (pin "D13") (pinfunction "IO_L11P_T1_SRCC_15_D13") (pintype "bidirectional"))
      (node (ref "R695") (pin "2") (pinfunction "2_2") (pintype "passive"))
    )
    (net (code "85") (name "/Helper_DCXO_SCL") (class "Default")
      (node (ref "IC84") (pin "U14") (pinfunction "IO_L20P_T3_A08_D24_14_U14") (pintype "bidirectional"))
    )
    (net (code "86") (name "/Helper_DCXO_SDA") (class "Default")
      (node (ref "IC84") (pin "V14") (pinfunction "IO_L20N_T3_A07_D23_14_V14") (pintype "bidirectional"))
    )
    (net (code "87") (name "/I2C_SW_FPGA_RESETn") (class "Default")
      (node (ref "IC84") (pin "R15") (pinfunction "IO_L12N_T1_MRCC_14_R15") (pintype "bidirectional"))
    )
    (net (code "88") (name "/IO_CC_N") (class "Default")
      (node (ref "C893") (pin "2") (pinfunction "2_2") (pintype "passive"))
      (node (ref "R684") (pin "1") (pinfunction "1_1") (pintype "passive"))
    )
    (net (code "89") (name "/IO_CC_P") (class "Default")
      (node (ref "C894") (pin "2") (pinfunction "2_2") (pintype "passive"))
      (node (ref "R688") (pin "2") (pinfunction "2_2") (pintype "passive"))
    )
    (net (code "90") (name "/IO_L10_N") (class "Default")
      (node (ref "B26") (pin "1") (pinfunction "1_1") (pintype "passive"))
      (node (ref "IC84") (pin "V13") (pinfunction "IO_L21N_T3_DQS_A06_D22_14_V13") (pintype "bidirectional"))
    )
    (net (code "91") (name "/IO_L10_P") (class "Default")
      (node (ref "B27") (pin "1") (pinfunction "1_1") (pintype "passive"))
      (node (ref "IC84") (pin "V12") (pinfunction "IO_L21P_T3_DQS_14_V12") (pintype "bidirectional"))
    )
    (net (code "92") (name "/IO_L11_SRCC_N") (class "Default")
      (node (ref "B28") (pin "1") (pinfunction "1_1") (pintype "passive"))
      (node (ref "IC84") (pin "R17") (pinfunction "IO_L14N_T2_SRCC_14_R17") (pintype "bidirectional"))
    )
    (net (code "93") (name "/IO_L11_SRCC_P") (class "Default")
      (node (ref "B29") (pin "1") (pinfunction "1_1") (pintype "passive"))
      (node (ref "IC84") (pin "R16") (pinfunction "IO_L14P_T2_SRCC_14_R16") (pintype "bidirectional"))
    )
    (net (code "94") (name "/IO_L14_SRCC_N") (class "Default")
      (node (ref "B24") (pin "1") (pinfunction "1_1") (pintype "passive"))
      (node (ref "IC84") (pin "P16") (pinfunction "IO_L11N_T1_SRCC_14_P16") (pintype "bidirectional"))
    )
    (net (code "95") (name "/IO_L14_SRCC_P") (class "Default")
      (node (ref "B25") (pin "1") (pinfunction "1_1") (pintype "passive"))
      (node (ref "IC84") (pin "P15") (pinfunction "IO_L11P_T1_SRCC_14_P15") (pintype "bidirectional"))
    )
    (net (code "96") (name "/IO_L15_N") (class "Default")
      (node (ref "B22") (pin "1") (pinfunction "1_1") (pintype "passive"))
      (node (ref "IC84") (pin "V11") (pinfunction "IO_L23N_T3_A02_D18_14_V11") (pintype "bidirectional"))
    )
    (net (code "97") (name "/IO_L15_P") (class "Default")
      (node (ref "B23") (pin "1") (pinfunction "1_1") (pintype "passive"))
      (node (ref "IC84") (pin "U11") (pinfunction "IO_L23P_T3_A03_D19_14_U11") (pintype "bidirectional"))
    )
    (net (code "98") (name "/IO_L16_N") (class "Default")
      (node (ref "B20") (pin "1") (pinfunction "1_1") (pintype "passive"))
      (node (ref "IC84") (pin "V9") (pinfunction "IO_L24N_T3_A00_D16_14_V9") (pintype "bidirectional"))
    )
    (net (code "99") (name "/IO_L16_P") (class "Default")
      (node (ref "B21") (pin "1") (pinfunction "1_1") (pintype "passive"))
      (node (ref "IC84") (pin "U9") (pinfunction "IO_L24P_T3_A01_D17_14_U9") (pintype "bidirectional"))
    )
    (net (code "100") (name "/LED") (class "Default")
      (node (ref "IC84") (pin "D18") (pinfunction "IO_L17N_T2_A25_15_D18") (pintype "bidirectional"))
      (node (ref "R686") (pin "2") (pinfunction "2_2") (pintype "passive"))
      (node (ref "T22") (pin "1") (pinfunction "G_1") (pintype "passive"))
    )
    (net (code "101") (name "/LMK_CLK") (class "Default")
      (node (ref "IC84") (pin "N17") (pinfunction "IO_L9N_T1_DQS_D13_14_N17") (pintype "bidirectional"))
    )
    (net (code "102") (name "/LMK_DATA") (class "Default")
      (node (ref "IC84") (pin "N16") (pinfunction "IO_L9P_T1_DQS_14_N16") (pintype "bidirectional"))
    )
    (net (code "103") (name "/LMK_LE") (class "Default")
      (node (ref "IC84") (pin "N18") (pinfunction "IO_L10P_T1_D14_14_N18") (pintype "bidirectional"))
    )
    (net (code "104") (name "/LMK_MUXOUT") (class "Default")
      (node (ref "IC84") (pin "P18") (pinfunction "IO_L10N_T1_D15_14_P18") (pintype "bidirectional"))
    )
    (net (code "105") (name "/LVDS0_N") (class "Default")
      (node (ref "IC84") (pin "C8") (pinfunction "IO_L1N_T0_AD0N_15_C8") (pintype "bidirectional"))
    )
    (net (code "106") (name "/LVDS0_P") (class "Default")
      (node (ref "IC84") (pin "D8") (pinfunction "IO_L1P_T0_AD0P_15_D8") (pintype "bidirectional"))
    )
    (net (code "107") (name "/LVDS1_N") (class "Default")
      (node (ref "IC84") (pin "C9") (pinfunction "IO_L2N_T0_AD8N_15_C9") (pintype "bidirectional"))
    )
    (net (code "108") (name "/LVDS1_P") (class "Default")
      (node (ref "IC84") (pin "D9") (pinfunction "IO_L2P_T0_AD8P_15_D9") (pintype "bidirectional"))
    )
    (net (code "109") (name "/LVDS2_N") (class "Default")
      (node (ref "IC84") (pin "A9") (pinfunction "IO_L3N_T0_DQS_AD1N_15_A9") (pintype "bidirectional"))
    )
    (net (code "110") (name "/LVDS2_P") (class "Default")
      (node (ref "IC84") (pin "B9") (pinfunction "IO_L3P_T0_DQS_AD1P_15_B9") (pintype "bidirectional"))
    )
    (net (code "111") (name "/LVDS3_N") (class "Default")
      (node (ref "IC84") (pin "C18") (pinfunction "IO_L18N_T2_A23_15_C18") (pintype "bidirectional"))
    )
    (net (code "112") (name "/LVDS3_P") (class "Default")
      (node (ref "IC84") (pin "C17") (pinfunction "IO_L18P_T2_A24_15_C17") (pintype "bidirectional"))
    )
    (net (code "113") (name "/LVDS4_N") (class "Default")
      (node (ref "IC84") (pin "B17") (pinfunction "IO_L16N_T2_A27_15_B17") (pintype "bidirectional"))
    )
    (net (code "114") (name "/LVDS4_P") (class "Default")
      (node (ref "IC84") (pin "C16") (pinfunction "IO_L16P_T2_A28_15_C16") (pintype "bidirectional"))
    )
    (net (code "115") (name "/LVDS5_N") (class "Default")
      (node (ref "IC84") (pin "C12") (pinfunction "IO_L6N_T0_VREF_15_C12") (pintype "bidirectional"))
    )
    (net (code "116") (name "/LVDS5_P") (class "Default")
      (node (ref "IC84") (pin "D11") (pinfunction "IO_L6P_T0_15_D11") (pintype "bidirectional"))
    )
    (net (code "117") (name "/LVDS6_N") (class "Default")
      (node (ref "IC84") (pin "B11") (pinfunction "IO_L4N_T0_15_B11") (pintype "bidirectional"))
    )
    (net (code "118") (name "/LVDS6_P") (class "Default")
      (node (ref "IC84") (pin "C11") (pinfunction "IO_L4P_T0_15_C11") (pintype "bidirectional"))
    )
    (net (code "119") (name "/LVDS7_N") (class "Default")
      (node (ref "IC84") (pin "A10") (pinfunction "IO_L5N_T0_AD9N_15_A10") (pintype "bidirectional"))
    )
    (net (code "120") (name "/LVDS7_P") (class "Default")
      (node (ref "IC84") (pin "B10") (pinfunction "IO_L5P_T0_AD9P_15_B10") (pintype "bidirectional"))
    )
    (net (code "121") (name "/LVDS8_N") (class "Default")
      (node (ref "IC84") (pin "A12") (pinfunction "IO_L7N_T1_AD2N_15_A12") (pintype "bidirectional"))
    )
    (net (code "122") (name "/LVDS8_P") (class "Default")
      (node (ref "IC84") (pin "B12") (pinfunction "IO_L7P_T1_AD2P_15_B12") (pintype "bidirectional"))
    )
    (net (code "123") (name "/LVDS9_N") (class "Default")
      (node (ref "IC84") (pin "A14") (pinfunction "IO_L8N_T1_AD10N_15_A14") (pintype "bidirectional"))
    )
    (net (code "124") (name "/LVDS9_P") (class "Default")
      (node (ref "IC84") (pin "A13") (pinfunction "IO_L8P_T1_AD10P_15_A13") (pintype "bidirectional"))
    )
    (net (code "125") (name "/LVDS10_N") (class "Default")
      (node (ref "IC84") (pin "A17") (pinfunction "IO_L15N_T2_DQS_ADV_B_15_A17") (pintype "bidirectional"))
    )
    (net (code "126") (name "/LVDS10_P") (class "Default")
      (node (ref "IC84") (pin "B16") (pinfunction "IO_L15P_T2_DQS_15_B16") (pintype "bidirectional"))
    )
    (net (code "127") (name "/MISO_ADC0") (class "Default")
      (node (ref "IC84") (pin "J18") (pinfunction "IO_L3P_T0_DQS_PUDC_B_14_J18") (pintype "bidirectional"))
    )
    (net (code "128") (name "/MISO_ADC1") (class "Default")
      (node (ref "IC84") (pin "U17") (pinfunction "IO_L16N_T2_A15_D31_14_U17") (pintype "bidirectional"))
    )
    (net (code "129") (name "/MISO_DAC") (class "Default")
      (node (ref "IC84") (pin "J15") (pinfunction "IO_L2P_T0_D02_14_J15") (pintype "bidirectional"))
    )
    (net (code "130") (name "/MOSI") (class "Default")
      (node (ref "IC84") (pin "L14") (pinfunction "IO_0_14_L14") (pintype "bidirectional"))
    )
    (net (code "131") (name "/Main_DCXO_OE") (class "Default")
      (node (ref "IC84") (pin "M17") (pinfunction "IO_L7N_T1_D10_14_M17") (pintype "bidirectional"))
    )
    (net (code "132") (name "/Main_DCXO_SCL") (class "Default")
      (node (ref "IC84") (pin "U16") (pinfunction "IO_L17N_T2_A13_D29_14_U16") (pintype "bidirectional"))
    )
    (net (code "133") (name "/Main_DCXO_SDA") (class "Default")
      (node (ref "IC84") (pin "U15") (pinfunction "IO_L17P_T2_A14_D30_14_U15") (pintype "bidirectional"))
    )
    (net (code "134") (name "/REF2_N") (class "Default")
      (node (ref "IC84") (pin "D14") (pinfunction "IO_L12N_T1_MRCC_15_D14") (pintype "bidirectional"))
      (node (ref "R682") (pin "2") (pinfunction "2_2") (pintype "passive"))
    )
    (net (code "135") (name "/REF2_P") (class "Default")
      (node (ref "IC84") (pin "E13") (pinfunction "IO_L12P_T1_MRCC_15_E13") (pintype "bidirectional"))
      (node (ref "R683") (pin "2") (pinfunction "2_2") (pintype "passive"))
    )
    (net (code "136") (name "/RFSoC_Artix_0_N") (class "Default")
      (node (ref "IC84") (pin "E18") (pinfunction "IO_L24N_T3_RS0_15_E18") (pintype "bidirectional"))
      (node (ref "R665") (pin "2") (pinfunction "2_2") (pintype "passive"))
    )
    (net (code "137") (name "/RFSoC_Artix_0_P") (class "Default")
      (node (ref "IC84") (pin "F17") (pinfunction "IO_L24P_T3_RS1_15_F17") (pintype "bidirectional"))
      (node (ref "R600") (pin "2") (pinfunction "2_2") (pintype "passive"))
    )
    (net (code "138") (name "/RFSoC_Artix_1_N") (class "Default")
      (node (ref "IC84") (pin "H18") (pinfunction "IO_L23N_T3_FWE_B_15_H18") (pintype "bidirectional"))
      (node (ref "R581") (pin "2") (pinfunction "2_2") (pintype "passive"))
    )
    (net (code "139") (name "/RFSoC_Artix_1_P") (class "Default")
      (node (ref "IC84") (pin "H17") (pinfunction "IO_L23P_T3_FOE_B_15_H17") (pintype "bidirectional"))
      (node (ref "R543") (pin "2") (pinfunction "2_2") (pintype "passive"))
    )
    (net (code "140") (name "/RFSoC_Artix_2_N") (class "Default")
      (node (ref "IC84") (pin "F14") (pinfunction "IO_L22N_T3_A16_15_F14") (pintype "bidirectional"))
      (node (ref "R542") (pin "2") (pinfunction "2_2") (pintype "passive"))
    )
    (net (code "141") (name "/RFSoC_Artix_2_P") (class "Default")
      (node (ref "IC84") (pin "G14") (pinfunction "IO_L22P_T3_A17_15_G14") (pintype "bidirectional"))
      (node (ref "R532") (pin "2") (pinfunction "2_2") (pintype "passive"))
    )
    (net (code "142") (name "/RFSoC_Artix_3_N") (class "Default")
      (node (ref "IC84") (pin "F18") (pinfunction "IO_L19N_T3_A21_VREF_15_F18") (pintype "bidirectional"))
      (node (ref "R530") (pin "2") (pinfunction "2_2") (pintype "passive"))
    )
    (net (code "143") (name "/RFSoC_Artix_3_P") (class "Default")
      (node (ref "IC84") (pin "G17") (pinfunction "IO_L19P_T3_A22_15_G17") (pintype "bidirectional"))
      (node (ref "R525") (pin "2") (pinfunction "2_2") (pintype "passive"))
    )
    (net (code "144") (name "/SPI_CLK") (class "Default")
      (node (ref "IC84") (pin "K16") (pinfunction "IO_L1P_T0_D00_MOSI_14_K16") (pintype "bidirectional"))
    )
    (net (code "145") (name "/TCK") (class "Default")
      (node (ref "IC84") (pin "F8") (pinfunction "TCK_0_F8") (pintype "input"))
    )
    (net (code "146") (name "/TDI") (class "Default")
      (node (ref "IC84") (pin "T9") (pinfunction "TDI_0_T9") (pintype "input"))
    )
    (net (code "147") (name "/TDO") (class "Default")
      (node (ref "IC84") (pin "T8") (pinfunction "TDO_0_T8") (pintype "output"))
    )
    (net (code "148") (name "/TMS") (class "Default")
      (node (ref "IC84") (pin "R8") (pinfunction "TMS_0_R8") (pintype "input"))
    )
    (net (code "149") (name "/Vbias_0.9V") (class "Default")
      (node (ref "C1000") (pin "1") (pinfunction "1_1") (pintype "passive"))
      (node (ref "C1001") (pin "1") (pinfunction "1_1") (pintype "passive"))
      (node (ref "C998") (pin "1") (pinfunction "1_1") (pintype "passive"))
      (node (ref "C999") (pin "1") (pinfunction "1_1") (pintype "passive"))
      (node (ref "R669") (pin "2") (pinfunction "2_2") (pintype "passive"))
      (node (ref "R670") (pin "2") (pinfunction "2_2") (pintype "passive"))
      (node (ref "R685") (pin "2") (pinfunction "2_2") (pintype "passive"))
      (node (ref "R689") (pin "2") (pinfunction "2_2") (pintype "passive"))
    )
    (net (code "150") (name "/Vbias_1.25V") (class "Default")
      (node (ref "C475") (pin "1") (pinfunction "1_1") (pintype "passive"))
      (node (ref "C476") (pin "1") (pinfunction "1_1") (pintype "passive"))
      (node (ref "C481") (pin "1") (pinfunction "1_1") (pintype "passive"))
      (node (ref "C489") (pin "1") (pinfunction "1_1") (pintype "passive"))
      (node (ref "C898") (pin "1") (pinfunction "1_1") (pintype "passive"))
      (node (ref "C899") (pin "1") (pinfunction "1_1") (pintype "passive"))
      (node (ref "C900") (pin "1") (pinfunction "1_1") (pintype "passive"))
      (node (ref "C901") (pin "1") (pinfunction "1_1") (pintype "passive"))
      (node (ref "R525") (pin "1") (pinfunction "1_1") (pintype "passive"))
      (node (ref "R530") (pin "1") (pinfunction "1_1") (pintype "passive"))
      (node (ref "R532") (pin "1") (pinfunction "1_1") (pintype "passive"))
      (node (ref "R542") (pin "1") (pinfunction "1_1") (pintype "passive"))
      (node (ref "R543") (pin "1") (pinfunction "1_1") (pintype "passive"))
      (node (ref "R581") (pin "1") (pinfunction "1_1") (pintype "passive"))
      (node (ref "R600") (pin "1") (pinfunction "1_1") (pintype "passive"))
      (node (ref "R665") (pin "1") (pinfunction "1_1") (pintype "passive"))
      (node (ref "R682") (pin "1") (pinfunction "1_1") (pintype "passive"))
      (node (ref "R683") (pin "1") (pinfunction "1_1") (pintype "passive"))
      (node (ref "R691") (pin "1") (pinfunction "1_1") (pintype "passive"))
      (node (ref "R692") (pin "1") (pinfunction "1_1") (pintype "passive"))
      (node (ref "R693") (pin "1") (pinfunction "1_1") (pintype "passive"))
      (node (ref "R694") (pin "1") (pinfunction "1_1") (pintype "passive"))
      (node (ref "R695") (pin "1") (pinfunction "1_1") (pintype "passive"))
      (node (ref "R696") (pin "1") (pinfunction "1_1") (pintype "passive"))
      (node (ref "R706") (pin "2") (pinfunction "2_2") (pintype "passive"))
      (node (ref "R707") (pin "2") (pinfunction "2_2") (pintype "passive"))
    )
    (net (code "151") (name "/WR_CLK_SEL") (class "Default")
      (node (ref "IC84") (pin "M15") (pinfunction "IO_L6N_T0_D08_VREF_14_M15") (pintype "bidirectional"))
    )
    (net (code "152") (name "/WR_REF_CLK_IN_N") (class "Default")
      (node (ref "IC84") (pin "D16") (pinfunction "IO_L14N_T2_SRCC_15_D16") (pintype "bidirectional"))
      (node (ref "R691") (pin "2") (pinfunction "2_2") (pintype "passive"))
    )
    (net (code "153") (name "/WR_REF_CLK_IN_P") (class "Default")
      (node (ref "IC84") (pin "E16") (pinfunction "IO_L14P_T2_SRCC_15_E16") (pintype "bidirectional"))
      (node (ref "R692") (pin "2") (pinfunction "2_2") (pintype "passive"))
    )
    (net (code "166") (name "GND") (class "Default")
      (node (ref "C1000") (pin "2") (pinfunction "2_2") (pintype "passive"))
      (node (ref "C1001") (pin "2") (pinfunction "2_2") (pintype "passive"))
      (node (ref "C475") (pin "2") (pinfunction "2_2") (pintype "passive"))
      (node (ref "C476") (pin "2") (pinfunction "2_2") (pintype "passive"))
      (node (ref "C481") (pin "2") (pinfunction "2_2") (pintype "passive"))
      (node (ref "C489") (pin "2") (pinfunction "2_2") (pintype "passive"))
      (node (ref "C897") (pin "1") (pinfunction "1_1") (pintype "passive"))
      (node (ref "C898") (pin "2") (pinfunction "2_2") (pintype "passive"))
      (node (ref "C899") (pin "2") (pinfunction "2_2") (pintype "passive"))
      (node (ref "C900") (pin "2") (pinfunction "2_2") (pintype "passive"))
      (node (ref "C901") (pin "2") (pinfunction "2_2") (pintype "passive"))
      (node (ref "C998") (pin "2") (pinfunction "2_2") (pintype "passive"))
      (node (ref "C999") (pin "2") (pinfunction "2_2") (pintype "passive"))
      (node (ref "IC84") (pin "K10") (pinfunction "VP_0_K10") (pintype "input"))
      (node (ref "IC84") (pin "K9") (pinfunction "VREFN_0_K9") (pintype "input"))
      (node (ref "IC84") (pin "L10") (pinfunction "VREFP_0_L10") (pintype "input"))
      (node (ref "IC84") (pin "L9") (pinfunction "VN_0_L9") (pintype "input"))
      (node (ref "J22") (pin "2") (pinfunction "2_2") (pintype "bidirectional"))
      (node (ref "J23") (pin "2") (pinfunction "2_2") (pintype "bidirectional"))
      (node (ref "OSC7") (pin "2") (pinfunction "GND_2") (pintype "power_in"))
      (node (ref "R670") (pin "1") (pinfunction "1_1") (pintype "passive"))
      (node (ref "R686") (pin "1") (pinfunction "1_1") (pintype "passive"))
      (node (ref "R702") (pin "1") (pinfunction "1_1") (pintype "passive"))
      (node (ref "R703") (pin "1") (pinfunction "1_1") (pintype "passive"))
      (node (ref "R704") (pin "1") (pinfunction "1_1") (pintype "passive"))
      (node (ref "R705") (pin "1") (pinfunction "1_1") (pintype "passive"))
      (node (ref "R707") (pin "1") (pinfunction "1_1") (pintype "passive"))
      (node (ref "T22") (pin "2") (pinfunction "S_2") (pintype "passive"))
      (node (ref "T23") (pin "2") (pinfunction "S_2") (pintype "passive"))
    )
    (net (code "167") (name "Net-(IC84D-CFGBVS_0)") (class "Default")
      (node (ref "IC84") (pin "E12") (pinfunction "CFGBVS_0_E12") (pintype "input"))
      (node (ref "R711") (pin "2") (pinfunction "2_2") (pintype "passive"))
    )
    (net (code "168") (name "Net-(IC84D-M0_0)") (class "Default")
      (node (ref "IC84") (pin "R12") (pinfunction "M0_0_R12") (pintype "input"))
      (node (ref "R708") (pin "2") (pinfunction "2_2") (pintype "passive"))
    )
    (net (code "169") (name "Net-(IC84D-M1_0)") (class "Default")
      (node (ref "IC84") (pin "R11") (pinfunction "M1_0_R11") (pintype "input"))
      (node (ref "R709") (pin "2") (pinfunction "2_2") (pintype "passive"))
    )
    (net (code "170") (name "Net-(IC84D-M2_0)") (class "Default")
      (node (ref "IC84") (pin "F13") (pinfunction "M2_0_F13") (pintype "input"))
      (node (ref "R710") (pin "2") (pinfunction "2_2") (pintype "passive"))
    )
    (net (code "171") (name "Net-(LD15-A)") (class "Default")
      (node (ref "LD15") (pin "2") (pinfunction "A_2") (pintype "passive"))
      (node (ref "R681") (pin "1") (pinfunction "1_1") (pintype "passive"))
    )
    (net (code "172") (name "Net-(LD15-C)") (class "Default")
      (node (ref "LD15") (pin "1") (pinfunction "C_1") (pintype "passive"))
      (node (ref "T22") (pin "3") (pinfunction "D_3") (pintype "passive"))
    )
    (net (code "173") (name "Net-(LD16-A)") (class "Default")
      (node (ref "LD16") (pin "2") (pinfunction "A_2") (pintype "passive"))
      (node (ref "R712") (pin "1") (pinfunction "1_1") (pintype "passive"))
    )
    (net (code "174") (name "Net-(LD16-C)") (class "Default")
      (node (ref "LD16") (pin "1") (pinfunction "C_1") (pintype "passive"))
      (node (ref "T23") (pin "3") (pinfunction "D_3") (pintype "passive"))
    )
    (net (code "175") (name "Net-(OSC7-OUT)") (class "Default")
      (node (ref "OSC7") (pin "3") (pinfunction "OUT_3") (pintype "output"))
      (node (ref "R698") (pin "1") (pinfunction "1_1") (pintype "passive"))
    )
    (net (code "176") (name "P1V8") (class "Default")
      (node (ref "R669") (pin "1") (pinfunction "1_1") (pintype "passive"))
    )
    (net (code "177") (name "P2V5") (class "Default")
      (node (ref "R697") (pin "1") (pinfunction "1_1") (pintype "passive"))
      (node (ref "R699") (pin "1") (pinfunction "1_1") (pintype "passive"))
      (node (ref "R700") (pin "1") (pinfunction "1_1") (pintype "passive"))
      (node (ref "R701") (pin "1") (pinfunction "1_1") (pintype "passive"))
      (node (ref "R706") (pin "1") (pinfunction "1_1") (pintype "passive"))
    )
    (net (code "178") (name "P3V3") (class "Default")
      (node (ref "C897") (pin "2") (pinfunction "2_2") (pintype "passive"))
      (node (ref "OSC7") (pin "1") (pinfunction "OE_1") (pintype "input"))
      (node (ref "OSC7") (pin "4") (pinfunction "VCC_4") (pintype "power_in"))
      (node (ref "R427") (pin "2") (pinfunction "2_2") (pintype "passive"))
      (node (ref "R428") (pin "2") (pinfunction "2_2") (pintype "passive"))
      (node (ref "R681") (pin "2") (pinfunction "2_2") (pintype "passive"))
      (node (ref "R708") (pin "1") (pinfunction "1_1") (pintype "passive"))
      (node (ref "R709") (pin "1") (pinfunction "1_1") (pintype "passive"))
      (node (ref "R710") (pin "1") (pinfunction "1_1") (pintype "passive"))
      (node (ref "R711") (pin "1") (pinfunction "1_1") (pintype "passive"))
      (node (ref "R712") (pin "2") (pinfunction "2_2") (pintype "passive"))
    )
    (net (code "179") (name "unconnected-(IC84A-IO_25_14-PadU10)") (class "Default")
      (node (ref "IC84") (pin "U10") (pinfunction "IO_25_14_U10") (pintype "bidirectional"))
    )
    (net (code "180") (name "unconnected-(IC84A-IO_L2N_T0_D03_14-PadJ16)") (class "Default")
      (node (ref "IC84") (pin "J16") (pinfunction "IO_L2N_T0_D03_14_J16") (pintype "bidirectional"))
    )
    (net (code "181") (name "unconnected-(IC84A-IO_L3N_T0_DQS_EMCCLK_14-PadK18)") (class "Default")
      (node (ref "IC84") (pin "K18") (pinfunction "IO_L3N_T0_DQS_EMCCLK_14_K18") (pintype "bidirectional"))
    )
    (net (code "182") (name "unconnected-(IC84A-IO_L4N_T0_D05_14-PadL18)") (class "Default")
      (node (ref "IC84") (pin "L18") (pinfunction "IO_L4N_T0_D05_14_L18") (pintype "bidirectional"))
    )
    (net (code "183") (name "unconnected-(IC84A-IO_L4P_T0_D04_14-PadK17)") (class "Default")
      (node (ref "IC84") (pin "K17") (pinfunction "IO_L4P_T0_D04_14_K17") (pintype "bidirectional"))
    )
    (net (code "184") (name "unconnected-(IC84A-IO_L5N_T0_D07_14-PadK15)") (class "Default")
      (node (ref "IC84") (pin "K15") (pinfunction "IO_L5N_T0_D07_14_K15") (pintype "bidirectional"))
    )
    (net (code "185") (name "unconnected-(IC84A-IO_L5P_T0_D06_14-PadJ14)") (class "Default")
      (node (ref "IC84") (pin "J14") (pinfunction "IO_L5P_T0_D06_14_J14") (pintype "bidirectional"))
    )
    (net (code "186") (name "unconnected-(IC84A-IO_L6P_T0_FCS_B_14-PadL15)") (class "Default")
      (node (ref "IC84") (pin "L15") (pinfunction "IO_L6P_T0_FCS_B_14_L15") (pintype "bidirectional"))
    )
    (net (code "187") (name "unconnected-(IC84A-IO_L12P_T1_MRCC_14-PadP14)") (class "Default")
      (node (ref "IC84") (pin "P14") (pinfunction "IO_L12P_T1_MRCC_14_P14") (pintype "bidirectional"))
    )
    (net (code "188") (name "unconnected-(IC84A-IO_L13N_T2_MRCC_14-PadT15)") (class "Default")
      (node (ref "IC84") (pin "T15") (pinfunction "IO_L13N_T2_MRCC_14_T15") (pintype "bidirectional"))
    )
    (net (code "189") (name "unconnected-(IC84A-IO_L18N_T2_A11_D27_14-PadV17)") (class "Default")
      (node (ref "IC84") (pin "V17") (pinfunction "IO_L18N_T2_A11_D27_14_V17") (pintype "bidirectional"))
    )
    (net (code "190") (name "unconnected-(IC84A-IO_L18P_T2_A12_D28_14-PadV16)") (class "Default")
      (node (ref "IC84") (pin "V16") (pinfunction "IO_L18P_T2_A12_D28_14_V16") (pintype "bidirectional"))
    )
    (net (code "191") (name "unconnected-(IC84A-IO_L22N_T3_A04_D20_14-PadU12)") (class "Default")
      (node (ref "IC84") (pin "U12") (pinfunction "IO_L22N_T3_A04_D20_14_U12") (pintype "bidirectional"))
    )
    (net (code "192") (name "unconnected-(IC84A-IO_L22P_T3_A05_D21_14-PadT12)") (class "Default")
      (node (ref "IC84") (pin "T12") (pinfunction "IO_L22P_T3_A05_D21_14_T12") (pintype "bidirectional"))
    )
    (net (code "193") (name "unconnected-(IC84B-IO_0_15-PadD10)") (class "Default")
      (node (ref "IC84") (pin "D10") (pinfunction "IO_0_15_D10") (pintype "bidirectional+no_connect"))
    )
    (net (code "194") (name "unconnected-(IC84B-IO_25_15-PadH14)") (class "Default")
      (node (ref "IC84") (pin "H14") (pinfunction "IO_25_15_H14") (pintype "bidirectional"))
    )
    (net (code "195") (name "unconnected-(IC84B-IO_L17P_T2_A26_15-PadE17)") (class "Default")
      (node (ref "IC84") (pin "E17") (pinfunction "IO_L17P_T2_A26_15_E17") (pintype "bidirectional"))
    )
    (net (code "196") (name "unconnected-(IC84B-IO_L20N_T3_A19_15-PadG16)") (class "Default")
      (node (ref "IC84") (pin "G16") (pinfunction "IO_L20N_T3_A19_15_G16") (pintype "bidirectional"))
    )
    (net (code "197") (name "unconnected-(IC84B-IO_L20P_T3_A20_15-PadH16)") (class "Default")
      (node (ref "IC84") (pin "H16") (pinfunction "IO_L20P_T3_A20_15_H16") (pintype "bidirectional"))
    )
    (net (code "198") (name "unconnected-(IC84B-IO_L21N_T3_DQS_A18_15-PadF15)") (class "Default")
      (node (ref "IC84") (pin "F15") (pinfunction "IO_L21N_T3_DQS_A18_15_F15") (pintype "bidirectional"))
    )
    (net (code "199") (name "unconnected-(IC84B-IO_L21P_T3_DQS_15-PadG15)") (class "Default")
      (node (ref "IC84") (pin "G15") (pinfunction "IO_L21P_T3_DQS_15_G15") (pintype "bidirectional"))
    )
    (net (code "200") (name "unconnected-(IC84C-IO_L10N_T1_34-PadN4)") (class "Default")
      (node (ref "IC84") (pin "N4") (pinfunction "IO_L10N_T1_34_N4") (pintype "bidirectional"))
    )
    (net (code "201") (name "unconnected-(IC84C-IO_L11N_T1_SRCC_34-PadN2)") (class "Default")
      (node (ref "IC84") (pin "N2") (pinfunction "IO_L11N_T1_SRCC_34_N2") (pintype "bidirectional"))
    )
    (net (code "202") (name "unconnected-(IC84C-IO_L11P_T1_SRCC_34-PadN3)") (class "Default")
      (node (ref "IC84") (pin "N3") (pinfunction "IO_L11P_T1_SRCC_34_N3") (pintype "bidirectional"))
    )
    (net (code "203") (name "unconnected-(IC84C-IO_L13N_T2_MRCC_34-PadR1)") (class "Default")
      (node (ref "IC84") (pin "R1") (pinfunction "IO_L13N_T2_MRCC_34_R1") (pintype "bidirectional"))
    )
    (net (code "204") (name "unconnected-(IC84C-IO_L13P_T2_MRCC_34-PadR2)") (class "Default")
      (node (ref "IC84") (pin "R2") (pinfunction "IO_L13P_T2_MRCC_34_R2") (pintype "bidirectional"))
    )
    (net (code "205") (name "unconnected-(IC84C-IO_L14N_T2_SRCC_34-PadT2)") (class "Default")
      (node (ref "IC84") (pin "T2") (pinfunction "IO_L14N_T2_SRCC_34_T2") (pintype "bidirectional"))
    )
    (net (code "206") (name "unconnected-(IC84C-IO_L14P_T2_SRCC_34-PadR3)") (class "Default")
      (node (ref "IC84") (pin "R3") (pinfunction "IO_L14P_T2_SRCC_34_R3") (pintype "bidirectional"))
    )
    (net (code "207") (name "unconnected-(IC84C-IO_L15P_T2_DQS_34-PadU2)") (class "Default")
      (node (ref "IC84") (pin "U2") (pinfunction "IO_L15P_T2_DQS_34_U2") (pintype "bidirectional"))
    )
  )
)
